# FuenteDeAlimentacion_SCH.net
KiCad netlist of a schematic drawn in Altium Designer
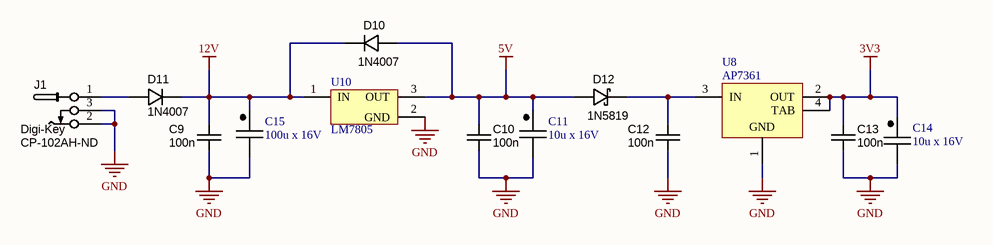
[diagram p0: FuenteDeAlimentacion_SCH.SchDoc]

(export (version "E")
  (design (tool "Eeschema 10.0.6"))
  (components
    (comp (ref "C9")
      (value "100n")
      (footprint "CAPC1608X90N")
      (description "Capacitor SMD Cer 100nF 10% 50V X7R 0603")
      (fields (field (name "TOLERANCE") "±10%"))
      (libsource (lib "PBL - Capacitors") (part "CAPC_47n_0603_X7R_50V_10%"))
    )
    (comp (ref "C10")
      (value "100n")
      (footprint "CAPC1608X90N")
      (description "Capacitor SMD Cer 100nF 10% 50V X7R 0603")
      (fields (field (name "TOLERANCE") "±10%"))
      (libsource (lib "PBL - Capacitors") (part "CAPC_47n_0603_X7R_50V_10%"))
    )
    (comp (ref "C11")
      (value "10u x 16V")
      (footprint "CAP_Elec_5x5.7")
      (libsource (lib "Ampli_Lib_Sch") (part "CAP_Elec_4x4"))
    )
    (comp (ref "C12")
      (value "100n")
      (footprint "CAPC1608X90N")
      (description "Capacitor SMD Cer 100nF 10% 50V X7R 0603")
      (fields (field (name "TOLERANCE") "±10%"))
      (libsource (lib "PBL - Capacitors") (part "CAPC_47n_0603_X7R_50V_10%"))
    )
    (comp (ref "C13")
      (value "100n")
      (footprint "CAPC1608X90N")
      (description "Capacitor SMD Cer 100nF 10% 50V X7R 0603")
      (fields (field (name "TOLERANCE") "±10%"))
      (libsource (lib "PBL - Capacitors") (part "CAPC_47n_0603_X7R_50V_10%"))
    )
    (comp (ref "C14")
      (value "10u x 16V")
      (footprint "CAP_Elec_5x5.7")
      (libsource (lib "Ampli_Lib_Sch") (part "CAP_Elec_4x4"))
    )
    (comp (ref "C15")
      (value "100u x 16V")
      (footprint "CAP_ELEC_6.3X4.2")
      (libsource (lib "Ampli_Lib_Sch") (part "CAP_Elec_6.2x6.2"))
    )
    (comp (ref "D10")
      (value "1N4007")
      (footprint "DO-214AC")
      (description "Diode 1N4007 SMD DO-214AC 100V 1.5A SMA")
      (fields (field (name "MANUFACTURER PART NUMBER 1") "1N4007"))
      (libsource (lib "PBL - Diodes") (part "DIODE_100V_1.5A_SMA"))
    )
    (comp (ref "D11")
      (value "1N4007")
      (footprint "DO-214AC")
      (description "Diode 1N4007 SMD DO-214AC 100V 1.5A SMA")
      (fields (field (name "MANUFACTURER PART NUMBER 1") "1N4007"))
      (libsource (lib "PBL - Diodes") (part "DIODE_100V_1.5A_SMA"))
    )
    (comp (ref "D12")
      (value "1N5819")
      (footprint "SOD123")
      (description "Diode Schottky SMD 40V 1A SOD123")
      (fields (field (name "MANUFACTURER PART NUMBER 1") "1N5819"))
      (libsource (lib "PBL - Diodes") (part "DIODE_SCHOTTKY_40V_1A"))
    )
    (comp (ref "J1")
      (value "CONN_PWR_JACK_2.1x5.5mm")
      (footprint "CONN_PWR_JACK_2.1x5.5mm")
      (description "Power Connector, THT, 2.1mm ID, 5.5mm OD")
      (fields (field (name "SUPPLIER 1") "Digi-Key") (field (name "SUPPLIER PART NUMBER 1") "CP-102AH-ND"))
      (libsource (lib "PBL - Connectors") (part "CONN_PWR_JACK_2.1x5.5mm"))
    )
    (comp (ref "U8")
      (value "AP7361")
      (footprint "MP04A_L")
      (description "800mA Low-Dropout Linear Regulator, 4-pin SOT-223")
      (fields
        (field (name "MANUFACTURER") "National Semiconductor")
        (field (name "PARTNUMBER") "LM1117MPX-1.8")
      )
      (libsource (lib "Altium Content Vault") (part "CMP-0062-01652-3"))
    )
    (comp (ref "U10")
      (value "LM7805")
      (footprint "TO-220 FLAT")
      (description "Regulador LM7805 Flat TO-220")
      (libsource (lib "Ampli_Lib_Sch") (part "LM7805"))
    )
  )
  (nets
    (net (code "1") (name "3V3") (class "Default")
      (node (ref "C13") (pin "1") (pintype "passive"))
      (node (ref "C14") (pin "1") (pinfunction "1_1") (pintype "passive"))
      (node (ref "U8") (pin "2") (pinfunction "OUT_2") (pintype "power_in"))
      (node (ref "U8") (pin "4") (pinfunction "TAB_4") (pintype "power_in"))
    )
    (net (code "2") (name "5V") (class "Default")
      (node (ref "C10") (pin "1") (pintype "passive"))
      (node (ref "C11") (pin "1") (pinfunction "1_1") (pintype "passive"))
      (node (ref "D10") (pin "A") (pinfunction "A_A") (pintype "passive"))
      (node (ref "D12") (pin "A") (pinfunction "A_A") (pintype "passive"))
      (node (ref "U10") (pin "3") (pinfunction "OUT_3") (pintype "passive"))
    )
    (net (code "3") (name "12V") (class "Default")
      (node (ref "C15") (pin "1") (pinfunction "1_1") (pintype "passive"))
      (node (ref "C9") (pin "1") (pintype "passive"))
      (node (ref "D10") (pin "K") (pinfunction "K_K") (pintype "passive"))
      (node (ref "D11") (pin "K") (pinfunction "K_K") (pintype "passive"))
      (node (ref "U10") (pin "1") (pinfunction "IN_1") (pintype "passive"))
    )
    (net (code "4") (name "GND") (class "Default")
      (node (ref "C10") (pin "2") (pintype "passive"))
      (node (ref "C11") (pin "2") (pinfunction "2_2") (pintype "passive"))
      (node (ref "C12") (pin "2") (pintype "passive"))
      (node (ref "C13") (pin "2") (pintype "passive"))
      (node (ref "C14") (pin "2") (pinfunction "2_2") (pintype "passive"))
      (node (ref "C15") (pin "2") (pinfunction "2_2") (pintype "passive"))
      (node (ref "C9") (pin "2") (pintype "passive"))
      (node (ref "J1") (pin "2") (pinfunction "2_2") (pintype "passive"))
      (node (ref "J1") (pin "3") (pinfunction "3_3") (pintype "passive"))
      (node (ref "U10") (pin "2") (pinfunction "GND_2") (pintype "passive"))
      (node (ref "U8") (pin "1") (pinfunction "GND_1") (pintype "power_in"))
    )
    (net (code "5") (name "Net-(D11-PadA)") (class "Default")
      (node (ref "D11") (pin "A") (pinfunction "A_A") (pintype "passive"))
      (node (ref "J1") (pin "1") (pinfunction "1_1") (pintype "passive"))
    )
    (net (code "6") (name "Net-(U8-IN)") (class "Default")
      (node (ref "C12") (pin "1") (pintype "passive"))
      (node (ref "D12") (pin "K") (pinfunction "K_K") (pintype "passive"))
      (node (ref "U8") (pin "3") (pinfunction "IN_3") (pintype "power_in"))
    )
  )
)
